# etapa1_anger_X.net
KiCad netlist of a schematic drawn in Altium Designer
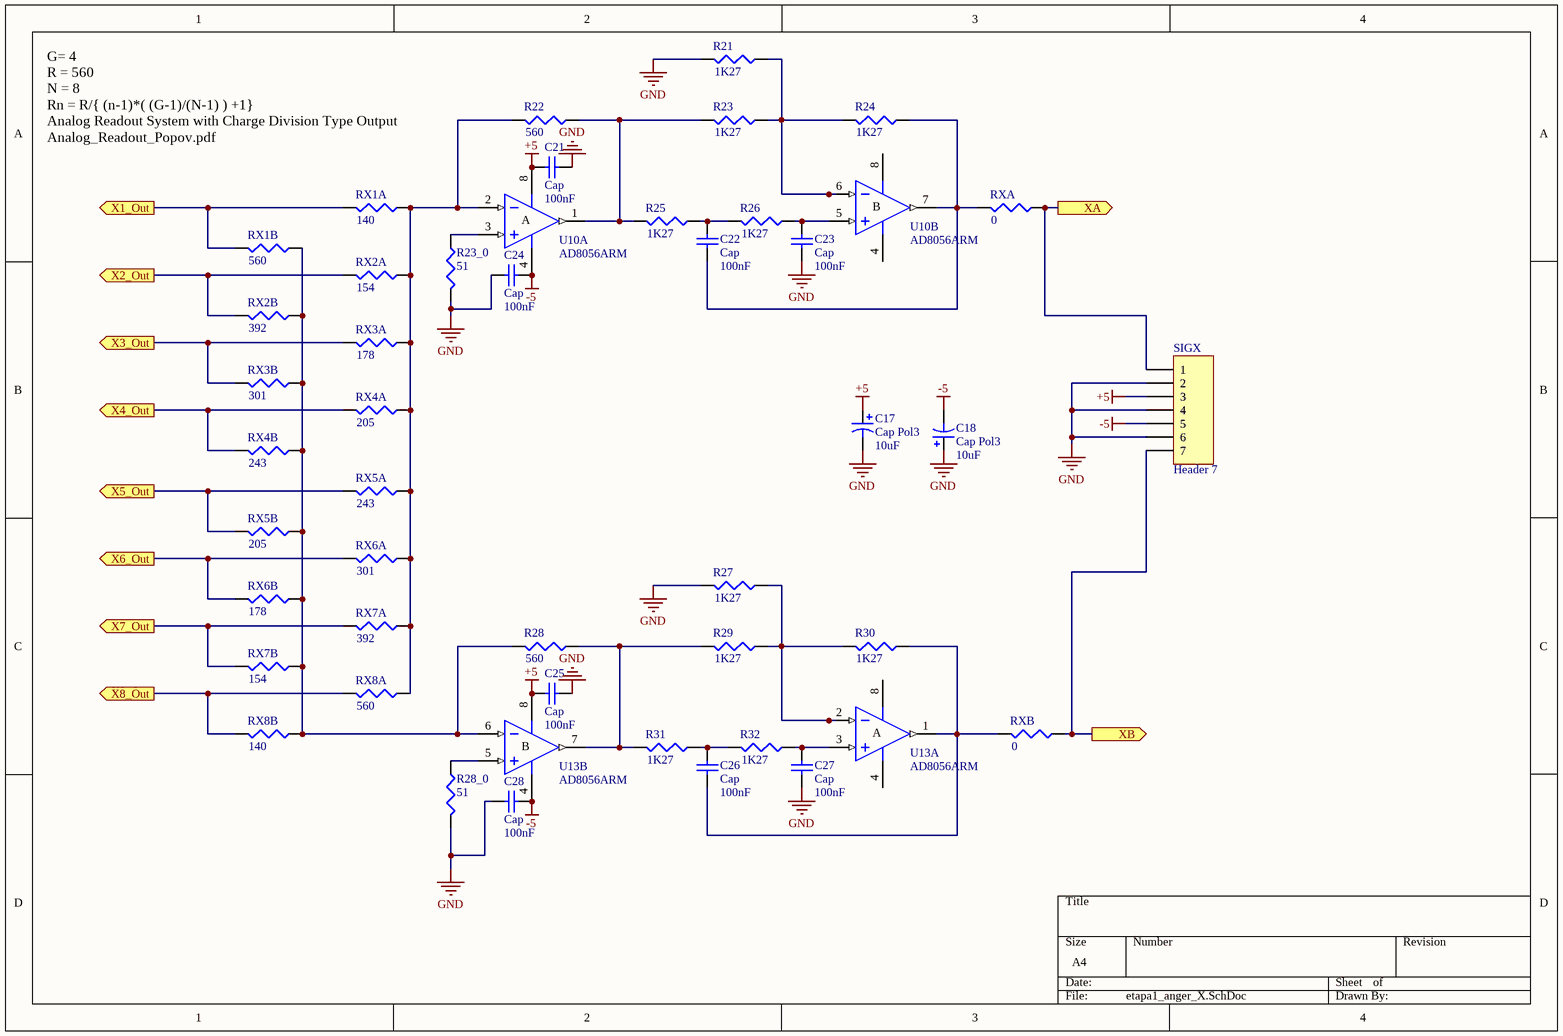
[diagram p0: etapa1_anger_X.SchDoc]

(export (version "E")
  (design (tool "Eeschema 10.0.6"))
  (components
    (comp (ref "C17")
      (value "Cap Pol3")
      (footprint "C0805")
      (description "Polarized Capacitor (Surface Mount)")
      (fields (field (name "ALTIUM_VALUE") "10uF") (field (name "PUBLISHER") "Altium Limited"))
      (libsource (lib "Miscellaneous Devices") (part "Cap Pol3"))
    )
    (comp (ref "C18")
      (value "Cap Pol3")
      (footprint "C0805")
      (description "Polarized Capacitor (Surface Mount)")
      (fields (field (name "ALTIUM_VALUE") "10uF") (field (name "PUBLISHER") "Altium Limited"))
      (libsource (lib "Miscellaneous Devices") (part "Cap Pol3"))
    )
    (comp (ref "C21")
      (value "Cap")
      (footprint "1608[0603]")
      (description "Capacitor")
      (fields (field (name "ALTIUM_VALUE") "100nF") (field (name "PUBLISHER") "Altium Limited"))
      (libsource (lib "Miscellaneous Devices") (part "Cap"))
    )
    (comp (ref "C22")
      (value "Cap")
      (footprint "1608[0603]")
      (description "Capacitor")
      (fields (field (name "ALTIUM_VALUE") "100nF") (field (name "PUBLISHER") "Altium Limited"))
      (libsource (lib "Miscellaneous Devices") (part "Cap"))
    )
    (comp (ref "C23")
      (value "Cap")
      (footprint "1608[0603]")
      (description "Capacitor")
      (fields (field (name "ALTIUM_VALUE") "100nF") (field (name "PUBLISHER") "Altium Limited"))
      (libsource (lib "Miscellaneous Devices") (part "Cap"))
    )
    (comp (ref "C24")
      (value "Cap")
      (footprint "1608[0603]")
      (description "Capacitor")
      (fields (field (name "ALTIUM_VALUE") "100nF") (field (name "PUBLISHER") "Altium Limited"))
      (libsource (lib "Miscellaneous Devices") (part "Cap"))
    )
    (comp (ref "C25")
      (value "Cap")
      (footprint "1608[0603]")
      (description "Capacitor")
      (fields (field (name "ALTIUM_VALUE") "100nF") (field (name "PUBLISHER") "Altium Limited"))
      (libsource (lib "Miscellaneous Devices") (part "Cap"))
    )
    (comp (ref "C26")
      (value "Cap")
      (footprint "1608[0603]")
      (description "Capacitor")
      (fields (field (name "ALTIUM_VALUE") "100nF") (field (name "PUBLISHER") "Altium Limited"))
      (libsource (lib "Miscellaneous Devices") (part "Cap"))
    )
    (comp (ref "C27")
      (value "Cap")
      (footprint "1608[0603]")
      (description "Capacitor")
      (fields (field (name "ALTIUM_VALUE") "100nF") (field (name "PUBLISHER") "Altium Limited"))
      (libsource (lib "Miscellaneous Devices") (part "Cap"))
    )
    (comp (ref "C28")
      (value "Cap")
      (footprint "1608[0603]")
      (description "Capacitor")
      (fields (field (name "ALTIUM_VALUE") "100nF") (field (name "PUBLISHER") "Altium Limited"))
      (libsource (lib "Miscellaneous Devices") (part "Cap"))
    )
    (comp (ref "R21")
      (value "1K27")
      (footprint "1608[0603]")
      (description "Resistor")
      (fields (field (name "Comment") "Res3") (field (name "PUBLISHER") "Altium Limited"))
      (libsource (lib "Miscellaneous Devices") (part "Res3"))
    )
    (comp (ref "R22")
      (value "560")
      (footprint "0402")
      (description "Resistor")
      (fields (field (name "Comment") "Res3") (field (name "PUBLISHER") "Altium Limited"))
      (libsource (lib "Miscellaneous Devices") (part "Res3"))
    )
    (comp (ref "R23")
      (value "1K27")
      (footprint "0402")
      (description "Resistor")
      (fields (field (name "Comment") "Res3") (field (name "PUBLISHER") "Altium Limited"))
      (libsource (lib "Miscellaneous Devices") (part "Res3"))
    )
    (comp (ref "R23_0")
      (value "51")
      (footprint "0402")
      (description "Resistor")
      (fields (field (name "Comment") "Res3") (field (name "PUBLISHER") "Altium Limited"))
      (libsource (lib "Miscellaneous Devices") (part "Res3"))
    )
    (comp (ref "R24")
      (value "1K27")
      (footprint "0402")
      (description "Resistor")
      (fields (field (name "Comment") "Res3") (field (name "PUBLISHER") "Altium Limited"))
      (libsource (lib "Miscellaneous Devices") (part "Res3"))
    )
    (comp (ref "R25")
      (value "1K27")
      (footprint "0402")
      (description "Resistor")
      (fields (field (name "Comment") "Res3") (field (name "PUBLISHER") "Altium Limited"))
      (libsource (lib "Miscellaneous Devices") (part "Res3"))
    )
    (comp (ref "R26")
      (value "1K27")
      (footprint "0402")
      (description "Resistor")
      (fields (field (name "Comment") "Res3") (field (name "PUBLISHER") "Altium Limited"))
      (libsource (lib "Miscellaneous Devices") (part "Res3"))
    )
    (comp (ref "R27")
      (value "1K27")
      (footprint "1608[0603]")
      (description "Resistor")
      (fields (field (name "Comment") "Res3") (field (name "PUBLISHER") "Altium Limited"))
      (libsource (lib "Miscellaneous Devices") (part "Res3"))
    )
    (comp (ref "R28")
      (value "560")
      (footprint "0402")
      (description "Resistor")
      (fields (field (name "Comment") "Res3") (field (name "PUBLISHER") "Altium Limited"))
      (libsource (lib "Miscellaneous Devices") (part "Res3"))
    )
    (comp (ref "R28_0")
      (value "51")
      (footprint "0402")
      (description "Resistor")
      (fields (field (name "Comment") "Res3") (field (name "PUBLISHER") "Altium Limited"))
      (libsource (lib "Miscellaneous Devices") (part "Res3"))
    )
    (comp (ref "R29")
      (value "1K27")
      (footprint "0402")
      (description "Resistor")
      (fields (field (name "Comment") "Res3") (field (name "PUBLISHER") "Altium Limited"))
      (libsource (lib "Miscellaneous Devices") (part "Res3"))
    )
    (comp (ref "R30")
      (value "1K27")
      (footprint "0402")
      (description "Resistor")
      (fields (field (name "Comment") "Res3") (field (name "PUBLISHER") "Altium Limited"))
      (libsource (lib "Miscellaneous Devices") (part "Res3"))
    )
    (comp (ref "R31")
      (value "1K27")
      (footprint "0402")
      (description "Resistor")
      (fields (field (name "Comment") "Res3") (field (name "PUBLISHER") "Altium Limited"))
      (libsource (lib "Miscellaneous Devices") (part "Res3"))
    )
    (comp (ref "R32")
      (value "1K27")
      (footprint "0402")
      (description "Resistor")
      (fields (field (name "Comment") "Res3") (field (name "PUBLISHER") "Altium Limited"))
      (libsource (lib "Miscellaneous Devices") (part "Res3"))
    )
    (comp (ref "RX1A")
      (value "140")
      (footprint "0402")
      (description "Resistor")
      (fields (field (name "Comment") "Res3") (field (name "PUBLISHER") "Altium Limited"))
      (libsource (lib "Miscellaneous Devices") (part "Res3"))
    )
    (comp (ref "RX1B")
      (value "560")
      (footprint "0402")
      (description "Resistor")
      (fields (field (name "Comment") "Res3") (field (name "PUBLISHER") "Altium Limited"))
      (libsource (lib "Miscellaneous Devices") (part "Res3"))
    )
    (comp (ref "RX2A")
      (value "154")
      (footprint "0402")
      (description "Resistor")
      (fields (field (name "Comment") "Res3") (field (name "PUBLISHER") "Altium Limited"))
      (libsource (lib "Miscellaneous Devices") (part "Res3"))
    )
    (comp (ref "RX2B")
      (value "392")
      (footprint "0402")
      (description "Resistor")
      (fields (field (name "Comment") "Res3") (field (name "PUBLISHER") "Altium Limited"))
      (libsource (lib "Miscellaneous Devices") (part "Res3"))
    )
    (comp (ref "RX3A")
      (value "178")
      (footprint "0402")
      (description "Resistor")
      (fields (field (name "Comment") "Res3") (field (name "PUBLISHER") "Altium Limited"))
      (libsource (lib "Miscellaneous Devices") (part "Res3"))
    )
    (comp (ref "RX3B")
      (value "301")
      (footprint "0402")
      (description "Resistor")
      (fields (field (name "Comment") "Res3") (field (name "PUBLISHER") "Altium Limited"))
      (libsource (lib "Miscellaneous Devices") (part "Res3"))
    )
    (comp (ref "RX4A")
      (value "205")
      (footprint "0402")
      (description "Resistor")
      (fields (field (name "Comment") "Res3") (field (name "PUBLISHER") "Altium Limited"))
      (libsource (lib "Miscellaneous Devices") (part "Res3"))
    )
    (comp (ref "RX4B")
      (value "243")
      (footprint "0402")
      (description "Resistor")
      (fields (field (name "Comment") "Res3") (field (name "PUBLISHER") "Altium Limited"))
      (libsource (lib "Miscellaneous Devices") (part "Res3"))
    )
    (comp (ref "RX5A")
      (value "243")
      (footprint "0402")
      (description "Resistor")
      (fields (field (name "Comment") "Res3") (field (name "PUBLISHER") "Altium Limited"))
      (libsource (lib "Miscellaneous Devices") (part "Res3"))
    )
    (comp (ref "RX5B")
      (value "205")
      (footprint "0402")
      (description "Resistor")
      (fields (field (name "Comment") "Res3") (field (name "PUBLISHER") "Altium Limited"))
      (libsource (lib "Miscellaneous Devices") (part "Res3"))
    )
    (comp (ref "RX6A")
      (value "301")
      (footprint "0402")
      (description "Resistor")
      (fields (field (name "Comment") "Res3") (field (name "PUBLISHER") "Altium Limited"))
      (libsource (lib "Miscellaneous Devices") (part "Res3"))
    )
    (comp (ref "RX6B")
      (value "178")
      (footprint "0402")
      (description "Resistor")
      (fields (field (name "Comment") "Res3") (field (name "PUBLISHER") "Altium Limited"))
      (libsource (lib "Miscellaneous Devices") (part "Res3"))
    )
    (comp (ref "RX7A")
      (value "392")
      (footprint "0402")
      (description "Resistor")
      (fields (field (name "Comment") "Res3") (field (name "PUBLISHER") "Altium Limited"))
      (libsource (lib "Miscellaneous Devices") (part "Res3"))
    )
    (comp (ref "RX7B")
      (value "154")
      (footprint "0402")
      (description "Resistor")
      (fields (field (name "Comment") "Res3") (field (name "PUBLISHER") "Altium Limited"))
      (libsource (lib "Miscellaneous Devices") (part "Res3"))
    )
    (comp (ref "RX8A")
      (value "560")
      (footprint "0402")
      (description "Resistor")
      (fields (field (name "Comment") "Res3") (field (name "PUBLISHER") "Altium Limited"))
      (libsource (lib "Miscellaneous Devices") (part "Res3"))
    )
    (comp (ref "RX8B")
      (value "140")
      (footprint "0402")
      (description "Resistor")
      (fields (field (name "Comment") "Res3") (field (name "PUBLISHER") "Altium Limited"))
      (libsource (lib "Miscellaneous Devices") (part "Res3"))
    )
    (comp (ref "RXA")
      (value "0")
      (footprint "0402")
      (description "Resistor")
      (fields (field (name "Comment") "Res3") (field (name "PUBLISHER") "Altium Limited"))
      (libsource (lib "Miscellaneous Devices") (part "Res3"))
    )
    (comp (ref "RXB")
      (value "0")
      (footprint "0402")
      (description "Resistor")
      (fields (field (name "Comment") "Res3") (field (name "PUBLISHER") "Altium Limited"))
      (libsource (lib "Miscellaneous Devices") (part "Res3"))
    )
    (comp (ref "SIGX")
      (value "Header 7")
      (footprint "HDR1X7")
      (description "Header, 7-Pin")
      (fields (field (name "PUBLISHER") "Altium Limited"))
      (libsource (lib "Miscellaneous Connectors") (part "Header 7"))
    )
    (comp (ref "U10")
      (value "AD8056ARM")
      (footprint "RM-8")
      (description "Low Cost, 300MHz Voltage Feedback Amplifier")
      (fields (field (name "PUBLISHER") "Altium Limited"))
      (libsource (lib "AD Operational Amplifier") (part "AD8056ARM"))
    )
    (comp (ref "U13")
      (value "AD8056ARM")
      (footprint "RM-8")
      (description "Low Cost, 300MHz Voltage Feedback Amplifier")
      (fields (field (name "PUBLISHER") "Altium Limited"))
      (libsource (lib "AD Operational Amplifier") (part "AD8056ARM"))
    )
  )
  (nets
    (net (code "1") (name "+5") (class "Default")
      (node (ref "C17") (pin "1") (pinfunction "1_1") (pintype "passive"))
      (node (ref "C21") (pin "1") (pinfunction "1_1") (pintype "passive"))
      (node (ref "C25") (pin "1") (pinfunction "1_1") (pintype "passive"))
      (node (ref "SIGX") (pin "3") (pinfunction "3_3") (pintype "passive"))
      (node (ref "U10") (pin "8") (pinfunction "V+_8") (pintype "power_in"))
      (node (ref "U13") (pin "8") (pinfunction "V+_8") (pintype "power_in"))
    )
    (net (code "2") (name "-5") (class "Default")
      (node (ref "C18") (pin "2") (pinfunction "2_2") (pintype "passive"))
      (node (ref "C24") (pin "2") (pinfunction "2_2") (pintype "passive"))
      (node (ref "C28") (pin "2") (pinfunction "2_2") (pintype "passive"))
      (node (ref "SIGX") (pin "5") (pinfunction "5_5") (pintype "passive"))
      (node (ref "U10") (pin "4") (pinfunction "V-_4") (pintype "power_in"))
      (node (ref "U13") (pin "4") (pinfunction "V-_4") (pintype "power_in"))
    )
    (net (code "3") (name "/X1_Out") (class "Default")
      (node (ref "RX1A") (pin "2") (pinfunction "2_2") (pintype "passive"))
      (node (ref "RX1B") (pin "2") (pinfunction "2_2") (pintype "passive"))
    )
    (net (code "4") (name "/X2_Out") (class "Default")
      (node (ref "RX2A") (pin "2") (pinfunction "2_2") (pintype "passive"))
      (node (ref "RX2B") (pin "2") (pinfunction "2_2") (pintype "passive"))
    )
    (net (code "5") (name "/X3_Out") (class "Default")
      (node (ref "RX3A") (pin "2") (pinfunction "2_2") (pintype "passive"))
      (node (ref "RX3B") (pin "2") (pinfunction "2_2") (pintype "passive"))
    )
    (net (code "6") (name "/X4_Out") (class "Default")
      (node (ref "RX4A") (pin "2") (pinfunction "2_2") (pintype "passive"))
      (node (ref "RX4B") (pin "2") (pinfunction "2_2") (pintype "passive"))
    )
    (net (code "7") (name "/X5_Out") (class "Default")
      (node (ref "RX5A") (pin "2") (pinfunction "2_2") (pintype "passive"))
      (node (ref "RX5B") (pin "2") (pinfunction "2_2") (pintype "passive"))
    )
    (net (code "8") (name "/X6_Out") (class "Default")
      (node (ref "RX6A") (pin "2") (pinfunction "2_2") (pintype "passive"))
      (node (ref "RX6B") (pin "2") (pinfunction "2_2") (pintype "passive"))
    )
    (net (code "9") (name "/X7_Out") (class "Default")
      (node (ref "RX7A") (pin "2") (pinfunction "2_2") (pintype "passive"))
      (node (ref "RX7B") (pin "2") (pinfunction "2_2") (pintype "passive"))
    )
    (net (code "10") (name "/X8_Out") (class "Default")
      (node (ref "RX8A") (pin "2") (pinfunction "2_2") (pintype "passive"))
      (node (ref "RX8B") (pin "2") (pinfunction "2_2") (pintype "passive"))
    )
    (net (code "11") (name "/XA") (class "Default")
      (node (ref "RXA") (pin "1") (pinfunction "1_1") (pintype "passive"))
      (node (ref "SIGX") (pin "1") (pinfunction "1_1") (pintype "passive"))
    )
    (net (code "12") (name "/XB") (class "Default")
      (node (ref "RXB") (pin "1") (pinfunction "1_1") (pintype "passive"))
      (node (ref "SIGX") (pin "7") (pinfunction "7_7") (pintype "passive"))
    )
    (net (code "13") (name "GND") (class "Default")
      (node (ref "C17") (pin "2") (pinfunction "2_2") (pintype "passive"))
      (node (ref "C18") (pin "1") (pinfunction "1_1") (pintype "passive"))
      (node (ref "C21") (pin "2") (pinfunction "2_2") (pintype "passive"))
      (node (ref "C23") (pin "2") (pinfunction "2_2") (pintype "passive"))
      (node (ref "C24") (pin "1") (pinfunction "1_1") (pintype "passive"))
      (node (ref "C25") (pin "2") (pinfunction "2_2") (pintype "passive"))
      (node (ref "C27") (pin "2") (pinfunction "2_2") (pintype "passive"))
      (node (ref "C28") (pin "1") (pinfunction "1_1") (pintype "passive"))
      (node (ref "R21") (pin "2") (pinfunction "2_2") (pintype "passive"))
      (node (ref "R23_0") (pin "2") (pinfunction "2_2") (pintype "passive"))
      (node (ref "R27") (pin "2") (pinfunction "2_2") (pintype "passive"))
      (node (ref "R28_0") (pin "2") (pinfunction "2_2") (pintype "passive"))
      (node (ref "SIGX") (pin "2") (pinfunction "2_2") (pintype "passive"))
      (node (ref "SIGX") (pin "4") (pinfunction "4_4") (pintype "passive"))
      (node (ref "SIGX") (pin "6") (pinfunction "6_6") (pintype "passive"))
    )
    (net (code "14") (name "Net-(C22-Pad1)") (class "Default")
      (node (ref "C22") (pin "1") (pinfunction "1_1") (pintype "passive"))
      (node (ref "R25") (pin "1") (pinfunction "1_1") (pintype "passive"))
      (node (ref "R26") (pin "2") (pinfunction "2_2") (pintype "passive"))
    )
    (net (code "15") (name "Net-(C26-Pad1)") (class "Default")
      (node (ref "C26") (pin "1") (pinfunction "1_1") (pintype "passive"))
      (node (ref "R31") (pin "1") (pinfunction "1_1") (pintype "passive"))
      (node (ref "R32") (pin "2") (pinfunction "2_2") (pintype "passive"))
    )
    (net (code "16") (name "Net-(U10A-IN+)") (class "Default")
      (node (ref "R23_0") (pin "1") (pinfunction "1_1") (pintype "passive"))
      (node (ref "U10") (pin "3") (pinfunction "IN+_3") (pintype "input"))
    )
    (net (code "17") (name "Net-(U10A-IN-)") (class "Default")
      (node (ref "R22") (pin "2") (pinfunction "2_2") (pintype "passive"))
      (node (ref "RX1A") (pin "1") (pinfunction "1_1") (pintype "passive"))
      (node (ref "RX2A") (pin "1") (pinfunction "1_1") (pintype "passive"))
      (node (ref "RX3A") (pin "1") (pinfunction "1_1") (pintype "passive"))
      (node (ref "RX4A") (pin "1") (pinfunction "1_1") (pintype "passive"))
      (node (ref "RX5A") (pin "1") (pinfunction "1_1") (pintype "passive"))
      (node (ref "RX6A") (pin "1") (pinfunction "1_1") (pintype "passive"))
      (node (ref "RX7A") (pin "1") (pinfunction "1_1") (pintype "passive"))
      (node (ref "RX8A") (pin "1") (pinfunction "1_1") (pintype "passive"))
      (node (ref "U10") (pin "2") (pinfunction "IN-_2") (pintype "input"))
    )
    (net (code "18") (name "Net-(U10A-OUT)") (class "Default")
      (node (ref "R22") (pin "1") (pinfunction "1_1") (pintype "passive"))
      (node (ref "R23") (pin "2") (pinfunction "2_2") (pintype "passive"))
      (node (ref "R25") (pin "2") (pinfunction "2_2") (pintype "passive"))
      (node (ref "U10") (pin "1") (pinfunction "OUT_1") (pintype "output"))
    )
    (net (code "19") (name "Net-(U10B-IN+)") (class "Default")
      (node (ref "C23") (pin "1") (pinfunction "1_1") (pintype "passive"))
      (node (ref "R26") (pin "1") (pinfunction "1_1") (pintype "passive"))
      (node (ref "U10") (pin "5") (pinfunction "IN+_5") (pintype "input"))
    )
    (net (code "20") (name "Net-(U10B-IN-)") (class "Default")
      (node (ref "R21") (pin "1") (pinfunction "1_1") (pintype "passive"))
      (node (ref "R23") (pin "1") (pinfunction "1_1") (pintype "passive"))
      (node (ref "R24") (pin "2") (pinfunction "2_2") (pintype "passive"))
      (node (ref "U10") (pin "6") (pinfunction "IN-_6") (pintype "input"))
    )
    (net (code "21") (name "Net-(U10B-OUT)") (class "Default")
      (node (ref "C22") (pin "2") (pinfunction "2_2") (pintype "passive"))
      (node (ref "R24") (pin "1") (pinfunction "1_1") (pintype "passive"))
      (node (ref "RXA") (pin "2") (pinfunction "2_2") (pintype "passive"))
      (node (ref "U10") (pin "7") (pinfunction "OUT_7") (pintype "output"))
    )
    (net (code "22") (name "Net-(U13A-IN+)") (class "Default")
      (node (ref "C27") (pin "1") (pinfunction "1_1") (pintype "passive"))
      (node (ref "R32") (pin "1") (pinfunction "1_1") (pintype "passive"))
      (node (ref "U13") (pin "3") (pinfunction "IN+_3") (pintype "input"))
    )
    (net (code "23") (name "Net-(U13A-IN-)") (class "Default")
      (node (ref "R27") (pin "1") (pinfunction "1_1") (pintype "passive"))
      (node (ref "R29") (pin "1") (pinfunction "1_1") (pintype "passive"))
      (node (ref "R30") (pin "2") (pinfunction "2_2") (pintype "passive"))
      (node (ref "U13") (pin "2") (pinfunction "IN-_2") (pintype "input"))
    )
    (net (code "24") (name "Net-(U13A-OUT)") (class "Default")
      (node (ref "C26") (pin "2") (pinfunction "2_2") (pintype "passive"))
      (node (ref "R30") (pin "1") (pinfunction "1_1") (pintype "passive"))
      (node (ref "RXB") (pin "2") (pinfunction "2_2") (pintype "passive"))
      (node (ref "U13") (pin "1") (pinfunction "OUT_1") (pintype "output"))
    )
    (net (code "25") (name "Net-(U13B-IN+)") (class "Default")
      (node (ref "R28_0") (pin "1") (pinfunction "1_1") (pintype "passive"))
      (node (ref "U13") (pin "5") (pinfunction "IN+_5") (pintype "input"))
    )
    (net (code "26") (name "Net-(U13B-IN-)") (class "Default")
      (node (ref "R28") (pin "2") (pinfunction "2_2") (pintype "passive"))
      (node (ref "RX1B") (pin "1") (pinfunction "1_1") (pintype "passive"))
      (node (ref "RX2B") (pin "1") (pinfunction "1_1") (pintype "passive"))
      (node (ref "RX3B") (pin "1") (pinfunction "1_1") (pintype "passive"))
      (node (ref "RX4B") (pin "1") (pinfunction "1_1") (pintype "passive"))
      (node (ref "RX5B") (pin "1") (pinfunction "1_1") (pintype "passive"))
      (node (ref "RX6B") (pin "1") (pinfunction "1_1") (pintype "passive"))
      (node (ref "RX7B") (pin "1") (pinfunction "1_1") (pintype "passive"))
      (node (ref "RX8B") (pin "1") (pinfunction "1_1") (pintype "passive"))
      (node (ref "U13") (pin "6") (pinfunction "IN-_6") (pintype "input"))
    )
    (net (code "27") (name "Net-(U13B-OUT)") (class "Default")
      (node (ref "R28") (pin "1") (pinfunction "1_1") (pintype "passive"))
      (node (ref "R29") (pin "2") (pinfunction "2_2") (pintype "passive"))
      (node (ref "R31") (pin "2") (pinfunction "2_2") (pintype "passive"))
      (node (ref "U13") (pin "7") (pinfunction "OUT_7") (pintype "output"))
    )
    (net (code "28") (name "unconnected-(U10B-V+-Pad8)") (class "Default")
      (node (ref "U10") (pin "8") (pinfunction "V+_8") (pintype "power_in"))
    )
    (net (code "29") (name "unconnected-(U10B-V--Pad4)") (class "Default")
      (node (ref "U10") (pin "4") (pinfunction "V-_4") (pintype "power_in"))
    )
    (net (code "30") (name "unconnected-(U13A-V+-Pad8)") (class "Default")
      (node (ref "U13") (pin "8") (pinfunction "V+_8") (pintype "power_in"))
    )
    (net (code "31") (name "unconnected-(U13A-V--Pad4)") (class "Default")
      (node (ref "U13") (pin "4") (pinfunction "V-_4") (pintype "power_in"))
    )
  )
)
